# Attiny_bot.net
KiCad netlist of a schematic drawn in EAGLE
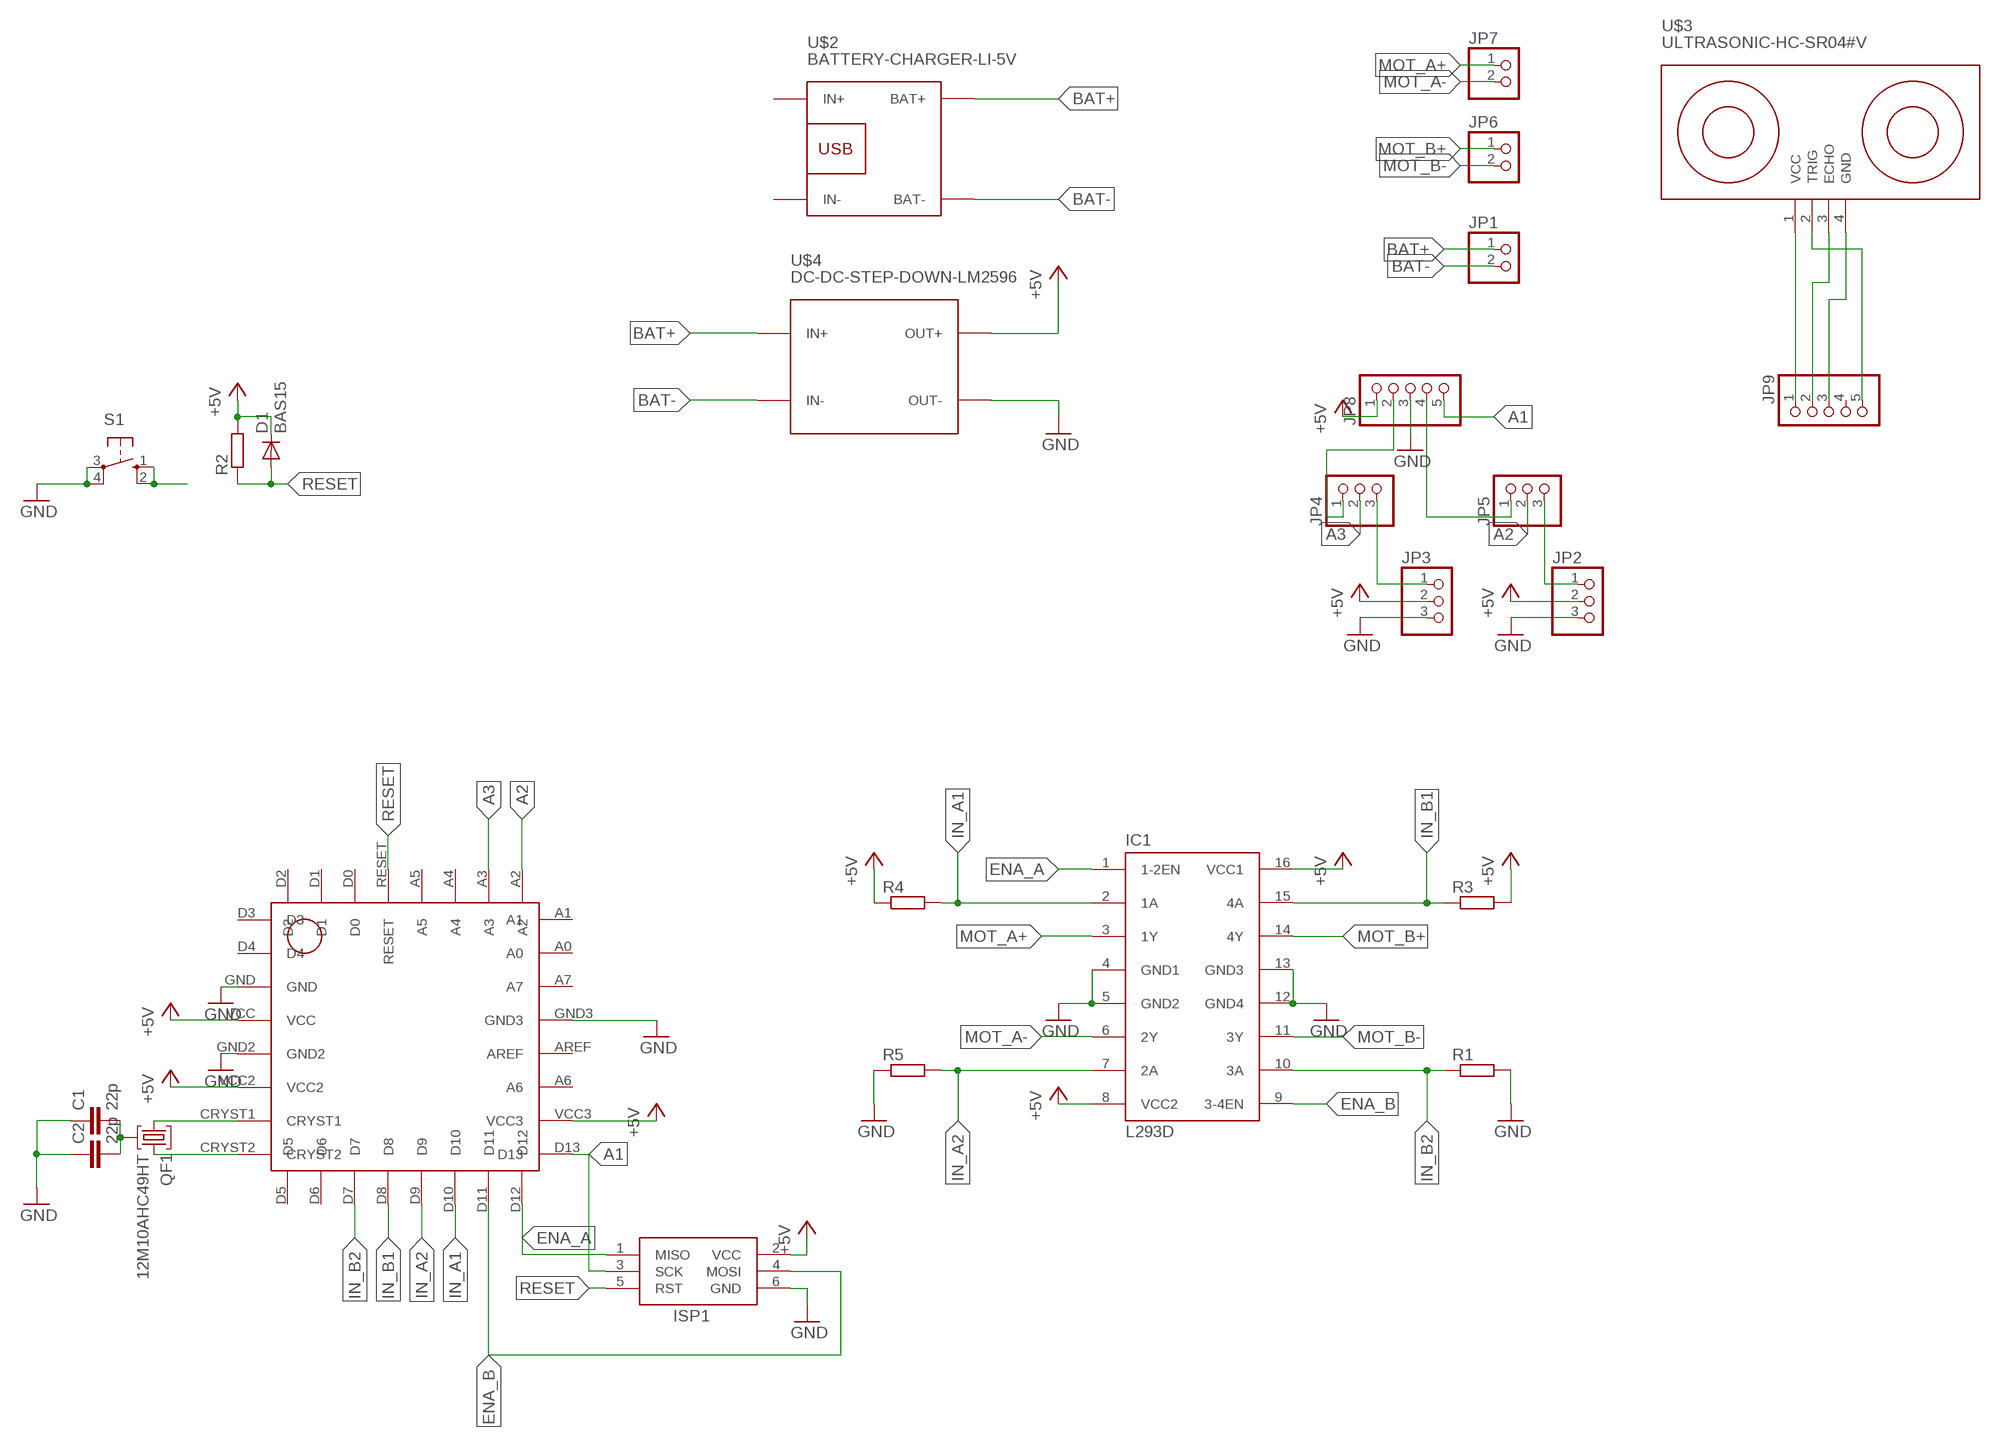
[diagram p0: schematic, sheet 1]

(export (version "E")
  (design (tool "Eeschema 10.0.6"))
  (components
    (comp (ref "C1")
      (value "22p")
      (footprint "eagle-import:C1206")
      (libsource (lib "eagle-import") (part "C-EUC1206"))
    )
    (comp (ref "C2")
      (value "22p")
      (footprint "eagle-import:C1206")
      (libsource (lib "eagle-import") (part "C-EUC1206"))
    )
    (comp (ref "D1")
      (value "BAS15")
      (footprint "eagle-import:DO34-7")
      (libsource (lib "eagle-import") (part "BAS15"))
    )
    (comp (ref "IC1")
      (value "L293D")
      (footprint "eagle-import:DIL16")
      (libsource (lib "eagle-import") (part "L293D"))
    )
    (comp (ref "ISP1")
      (value "AVRISP-6")
      (footprint "eagle-import:AVRISP")
      (libsource (lib "eagle-import") (part "AVRISP-6"))
    )
    (comp (ref "JP1")
      (value "PINHD-1X2")
      (footprint "eagle-import:1X02")
      (libsource (lib "eagle-import") (part "PINHD-1X2"))
    )
    (comp (ref "JP2")
      (value "PINHD-1X3")
      (footprint "eagle-import:1X03")
      (libsource (lib "eagle-import") (part "PINHD-1X3"))
    )
    (comp (ref "JP3")
      (value "PINHD-1X3")
      (footprint "eagle-import:1X03")
      (libsource (lib "eagle-import") (part "PINHD-1X3"))
    )
    (comp (ref "JP4")
      (value "PINHD-1X3")
      (footprint "eagle-import:1X03")
      (libsource (lib "eagle-import") (part "PINHD-1X3"))
    )
    (comp (ref "JP5")
      (value "PINHD-1X3")
      (footprint "eagle-import:1X03")
      (libsource (lib "eagle-import") (part "PINHD-1X3"))
    )
    (comp (ref "JP6")
      (value "PINHD-1X2")
      (footprint "eagle-import:1X02")
      (libsource (lib "eagle-import") (part "PINHD-1X2"))
    )
    (comp (ref "JP7")
      (value "PINHD-1X2")
      (footprint "eagle-import:1X02")
      (libsource (lib "eagle-import") (part "PINHD-1X2"))
    )
    (comp (ref "JP8")
      (value "PINHD-1X5")
      (footprint "eagle-import:1X05")
      (libsource (lib "eagle-import") (part "PINHD-1X5"))
    )
    (comp (ref "JP9")
      (value "PINHD-1X5")
      (footprint "eagle-import:1X05")
      (libsource (lib "eagle-import") (part "PINHD-1X5"))
    )
    (comp (ref "QF1")
      (value "12M10AHC49HT")
      (footprint "eagle-import:HC49U")
      (libsource (lib "eagle-import") (part "12M10AHC49HT"))
    )
    (comp (ref "R1")
      (value "R-EU_R1206")
      (footprint "eagle-import:R1206")
      (libsource (lib "eagle-import") (part "R-EU_R1206"))
    )
    (comp (ref "R2")
      (value "R-EU_R1206")
      (footprint "eagle-import:R1206")
      (libsource (lib "eagle-import") (part "R-EU_R1206"))
    )
    (comp (ref "R3")
      (value "R-EU_R1206")
      (footprint "eagle-import:R1206")
      (libsource (lib "eagle-import") (part "R-EU_R1206"))
    )
    (comp (ref "R4")
      (value "R-EU_R1206")
      (footprint "eagle-import:R1206")
      (libsource (lib "eagle-import") (part "R-EU_R1206"))
    )
    (comp (ref "R5")
      (value "R-EU_R1206")
      (footprint "eagle-import:R1206")
      (libsource (lib "eagle-import") (part "R-EU_R1206"))
    )
    (comp (ref "S1")
      (value "10-XX")
      (footprint "eagle-import:B3F-10XX")
      (fields (field (name "MPN") "B3F-1000"))
      (libsource (lib "eagle-import") (part "10-XX"))
    )
    (comp (ref "U$1")
      (value "PROCESSOR")
      (footprint "eagle-import:PROCESOR")
      (libsource (lib "eagle-import") (part "PROCESSOR"))
    )
    (comp (ref "U$2")
      (value "BATTERY-CHARGER-LI-5V")
      (footprint "eagle-import:BATTERY-CHARGER-LI-5V")
      (libsource (lib "eagle-import") (part "BATTERY-CHARGER-LI-5V"))
    )
    (comp (ref "U$3")
      (value "ULTRASONIC-HC-SR04#V")
      (footprint "eagle-import:ULTRASONIC-HC-SR04#V")
      (libsource (lib "eagle-import") (part "ULTRASONIC-HC-SR04#V"))
    )
    (comp (ref "U$4")
      (value "DC-DC-STEP-DOWN-LM2596")
      (footprint "eagle-import:DC-DC-STEP-DOWN-LM2596")
      (libsource (lib "eagle-import") (part "DC-DC-STEP-DOWN-LM2596"))
    )
  )
  (nets
    (net (code "1") (name "+5V") (class "Default")
      (node (ref "D1") (pin "C") (pinfunction "C_C") (pintype "passive"))
      (node (ref "IC1") (pin "16") (pinfunction "VCC1_16") (pintype "power_in"))
      (node (ref "IC1") (pin "8") (pinfunction "VCC2_8") (pintype "power_in"))
      (node (ref "ISP1") (pin "2") (pinfunction "VCC_2") (pintype "power_in"))
      (node (ref "JP2") (pin "2") (pinfunction "2_2") (pintype "passive"))
      (node (ref "JP3") (pin "2") (pinfunction "2_2") (pintype "passive"))
      (node (ref "JP8") (pin "1") (pinfunction "1_1") (pintype "passive"))
      (node (ref "R2") (pin "2") (pinfunction "2_2") (pintype "passive"))
      (node (ref "R3") (pin "2") (pinfunction "2_2") (pintype "passive"))
      (node (ref "R4") (pin "1") (pinfunction "1_1") (pintype "passive"))
      (node (ref "U$1") (pin "VCC") (pinfunction "VCC_VCC") (pintype "bidirectional"))
      (node (ref "U$1") (pin "VCC2") (pinfunction "VCC2_VCC2") (pintype "bidirectional"))
      (node (ref "U$1") (pin "VCC3") (pinfunction "VCC3_VCC3") (pintype "bidirectional"))
      (node (ref "U$4") (pin "OUT+") (pinfunction "OUT+_OUT+") (pintype "bidirectional"))
    )
    (net (code "2") (name "A1") (class "Default")
      (node (ref "ISP1") (pin "3") (pinfunction "SCK_3") (pintype "output"))
      (node (ref "JP8") (pin "5") (pinfunction "5_5") (pintype "passive"))
      (node (ref "U$1") (pin "D13") (pinfunction "D13_D13") (pintype "bidirectional"))
    )
    (net (code "3") (name "A2") (class "Default")
      (node (ref "JP5") (pin "2") (pinfunction "2_2") (pintype "passive"))
      (node (ref "U$1") (pin "A2") (pinfunction "A2_A2") (pintype "bidirectional"))
    )
    (net (code "4") (name "A3") (class "Default")
      (node (ref "JP4") (pin "2") (pinfunction "2_2") (pintype "passive"))
      (node (ref "U$1") (pin "A3") (pinfunction "A3_A3") (pintype "bidirectional"))
    )
    (net (code "5") (name "BAT+") (class "Default")
      (node (ref "JP1") (pin "1") (pinfunction "1_1") (pintype "passive"))
      (node (ref "U$2") (pin "BAT+") (pinfunction "BAT+_BAT+") (pintype "bidirectional"))
      (node (ref "U$4") (pin "IN+") (pinfunction "IN+_IN+") (pintype "bidirectional"))
    )
    (net (code "6") (name "BAT-") (class "Default")
      (node (ref "JP1") (pin "2") (pinfunction "2_2") (pintype "passive"))
      (node (ref "U$2") (pin "BAT-") (pinfunction "BAT-_BAT-") (pintype "bidirectional"))
      (node (ref "U$4") (pin "IN-") (pinfunction "IN-_IN-") (pintype "bidirectional"))
    )
    (net (code "7") (name "ENA_A") (class "Default")
      (node (ref "IC1") (pin "1") (pinfunction "1-2EN_1") (pintype "input"))
      (node (ref "ISP1") (pin "1") (pinfunction "MISO_1") (pintype "input"))
      (node (ref "U$1") (pin "D12") (pinfunction "D12_D12") (pintype "bidirectional"))
    )
    (net (code "8") (name "ENA_B") (class "Default")
      (node (ref "IC1") (pin "9") (pinfunction "3-4EN_9") (pintype "input"))
      (node (ref "ISP1") (pin "4") (pinfunction "MOSI_4") (pintype "output"))
      (node (ref "U$1") (pin "D11") (pinfunction "D11_D11") (pintype "bidirectional"))
    )
    (net (code "9") (name "GND") (class "Default")
      (node (ref "C1") (pin "1") (pinfunction "1_1") (pintype "passive"))
      (node (ref "C2") (pin "1") (pinfunction "1_1") (pintype "passive"))
      (node (ref "IC1") (pin "12") (pinfunction "GND4_12") (pintype "power_in"))
      (node (ref "IC1") (pin "13") (pinfunction "GND3_13") (pintype "power_in"))
      (node (ref "IC1") (pin "4") (pinfunction "GND1_4") (pintype "power_in"))
      (node (ref "IC1") (pin "5") (pinfunction "GND2_5") (pintype "power_in"))
      (node (ref "ISP1") (pin "6") (pinfunction "GND_6") (pintype "power_in"))
      (node (ref "JP2") (pin "3") (pinfunction "3_3") (pintype "passive"))
      (node (ref "JP3") (pin "3") (pinfunction "3_3") (pintype "passive"))
      (node (ref "JP8") (pin "3") (pinfunction "3_3") (pintype "passive"))
      (node (ref "R1") (pin "2") (pinfunction "2_2") (pintype "passive"))
      (node (ref "R5") (pin "1") (pinfunction "1_1") (pintype "passive"))
      (node (ref "S1") (pin "3") (pinfunction "P_3") (pintype "passive"))
      (node (ref "S1") (pin "4") (pinfunction "P1_4") (pintype "passive"))
      (node (ref "U$1") (pin "GND") (pinfunction "GND_GND") (pintype "bidirectional"))
      (node (ref "U$1") (pin "GND2") (pinfunction "GND2_GND2") (pintype "bidirectional"))
      (node (ref "U$1") (pin "GND3") (pinfunction "GND3_GND3") (pintype "bidirectional"))
      (node (ref "U$4") (pin "OUT-") (pinfunction "OUT-_OUT-") (pintype "bidirectional"))
    )
    (net (code "10") (name "IN_A1") (class "Default")
      (node (ref "IC1") (pin "2") (pinfunction "1A_2") (pintype "input"))
      (node (ref "R4") (pin "2") (pinfunction "2_2") (pintype "passive"))
      (node (ref "U$1") (pin "D10") (pinfunction "D10_D10") (pintype "bidirectional"))
    )
    (net (code "11") (name "IN_A2") (class "Default")
      (node (ref "IC1") (pin "7") (pinfunction "2A_7") (pintype "input"))
      (node (ref "R5") (pin "2") (pinfunction "2_2") (pintype "passive"))
      (node (ref "U$1") (pin "D9") (pinfunction "D9_D9") (pintype "bidirectional"))
    )
    (net (code "12") (name "IN_B1") (class "Default")
      (node (ref "IC1") (pin "15") (pinfunction "4A_15") (pintype "input"))
      (node (ref "R3") (pin "1") (pinfunction "1_1") (pintype "passive"))
      (node (ref "U$1") (pin "D8") (pinfunction "D8_D8") (pintype "bidirectional"))
    )
    (net (code "13") (name "IN_B2") (class "Default")
      (node (ref "IC1") (pin "10") (pinfunction "3A_10") (pintype "input"))
      (node (ref "R1") (pin "1") (pinfunction "1_1") (pintype "passive"))
      (node (ref "U$1") (pin "D7") (pinfunction "D7_D7") (pintype "bidirectional"))
    )
    (net (code "14") (name "MOT_A+") (class "Default")
      (node (ref "IC1") (pin "3") (pinfunction "1Y_3") (pintype "output"))
      (node (ref "JP7") (pin "1") (pinfunction "1_1") (pintype "passive"))
    )
    (net (code "15") (name "MOT_A-") (class "Default")
      (node (ref "IC1") (pin "6") (pinfunction "2Y_6") (pintype "output"))
      (node (ref "JP7") (pin "2") (pinfunction "2_2") (pintype "passive"))
    )
    (net (code "16") (name "MOT_B+") (class "Default")
      (node (ref "IC1") (pin "14") (pinfunction "4Y_14") (pintype "output"))
      (node (ref "JP6") (pin "1") (pinfunction "1_1") (pintype "passive"))
    )
    (net (code "17") (name "MOT_B-") (class "Default")
      (node (ref "IC1") (pin "11") (pinfunction "3Y_11") (pintype "output"))
      (node (ref "JP6") (pin "2") (pinfunction "2_2") (pintype "passive"))
    )
    (net (code "18") (name "Net-(C1-Pad2)") (class "Default")
      (node (ref "C1") (pin "2") (pinfunction "2_2") (pintype "passive"))
      (node (ref "C2") (pin "2") (pinfunction "2_2") (pintype "passive"))
      (node (ref "QF1") (pin "2") (pinfunction "2_2") (pintype "passive"))
    )
    (net (code "19") (name "Net-(JP2-Pad1)") (class "Default")
      (node (ref "JP2") (pin "1") (pinfunction "1_1") (pintype "passive"))
      (node (ref "JP5") (pin "3") (pinfunction "3_3") (pintype "passive"))
    )
    (net (code "20") (name "Net-(JP3-Pad1)") (class "Default")
      (node (ref "JP3") (pin "1") (pinfunction "1_1") (pintype "passive"))
      (node (ref "JP4") (pin "3") (pinfunction "3_3") (pintype "passive"))
    )
    (net (code "21") (name "Net-(JP4-Pad1)") (class "Default")
      (node (ref "JP4") (pin "1") (pinfunction "1_1") (pintype "passive"))
      (node (ref "JP8") (pin "2") (pinfunction "2_2") (pintype "passive"))
    )
    (net (code "22") (name "Net-(JP5-Pad1)") (class "Default")
      (node (ref "JP5") (pin "1") (pinfunction "1_1") (pintype "passive"))
      (node (ref "JP8") (pin "4") (pinfunction "4_4") (pintype "passive"))
    )
    (net (code "23") (name "Net-(QF1-Pad1)") (class "Default")
      (node (ref "QF1") (pin "1") (pinfunction "1_1") (pintype "passive"))
      (node (ref "U$1") (pin "CRYST1") (pinfunction "CRYST1_CRYST1") (pintype "bidirectional"))
    )
    (net (code "24") (name "Net-(QF1-Pad3)") (class "Default")
      (node (ref "QF1") (pin "3") (pinfunction "3_3") (pintype "passive"))
      (node (ref "U$1") (pin "CRYST2") (pinfunction "CRYST2_CRYST2") (pintype "bidirectional"))
    )
    (net (code "25") (name "Net-(S1-S)") (class "Default")
      (node (ref "S1") (pin "1") (pinfunction "S_1") (pintype "passive"))
      (node (ref "S1") (pin "2") (pinfunction "S1_2") (pintype "passive"))
    )
    (net (code "26") (name "Net-(U$3-ECHO)") (class "Default")
      (node (ref "JP9") (pin "2") (pinfunction "2_2") (pintype "passive"))
      (node (ref "U$3") (pin "3") (pinfunction "ECHO_3") (pintype "output"))
    )
    (net (code "27") (name "Net-(U$3-GND)") (class "Default")
      (node (ref "JP9") (pin "3") (pinfunction "3_3") (pintype "passive"))
      (node (ref "U$3") (pin "4") (pinfunction "GND_4") (pintype "power_in"))
    )
    (net (code "28") (name "Net-(U$3-TRIG)") (class "Default")
      (node (ref "JP9") (pin "5") (pinfunction "5_5") (pintype "passive"))
      (node (ref "U$3") (pin "2") (pinfunction "TRIG_2") (pintype "input"))
    )
    (net (code "29") (name "Net-(U$3-VCC)") (class "Default")
      (node (ref "JP9") (pin "1") (pinfunction "1_1") (pintype "passive"))
      (node (ref "U$3") (pin "1") (pinfunction "VCC_1") (pintype "power_in"))
    )
    (net (code "30") (name "RESET") (class "Default")
      (node (ref "D1") (pin "A") (pinfunction "A_A") (pintype "passive"))
      (node (ref "ISP1") (pin "5") (pinfunction "RST_5") (pintype "output"))
      (node (ref "R2") (pin "1") (pinfunction "1_1") (pintype "passive"))
      (node (ref "U$1") (pin "RESET") (pinfunction "RESET_RESET") (pintype "bidirectional"))
    )
    (net (code "31") (name "unconnected-(JP9-Pad4)") (class "Default")
      (node (ref "JP9") (pin "4") (pinfunction "4_4") (pintype "passive"))
    )
    (net (code "32") (name "unconnected-(U$1-PadA0)") (class "Default")
      (node (ref "U$1") (pin "A0") (pinfunction "A0_A0") (pintype "bidirectional"))
    )
    (net (code "33") (name "unconnected-(U$1-PadA1)") (class "Default")
      (node (ref "U$1") (pin "A1") (pinfunction "A1_A1") (pintype "bidirectional"))
    )
    (net (code "34") (name "unconnected-(U$1-PadA4)") (class "Default")
      (node (ref "U$1") (pin "A4") (pinfunction "A4_A4") (pintype "bidirectional"))
    )
    (net (code "35") (name "unconnected-(U$1-PadA5)") (class "Default")
      (node (ref "U$1") (pin "A5") (pinfunction "A5_A5") (pintype "bidirectional"))
    )
    (net (code "36") (name "unconnected-(U$1-PadA6)") (class "Default")
      (node (ref "U$1") (pin "A6") (pinfunction "A6_A6") (pintype "bidirectional"))
    )
    (net (code "37") (name "unconnected-(U$1-PadA7)") (class "Default")
      (node (ref "U$1") (pin "A7") (pinfunction "A7_A7") (pintype "bidirectional"))
    )
    (net (code "38") (name "unconnected-(U$1-PadAREF)") (class "Default")
      (node (ref "U$1") (pin "AREF") (pinfunction "AREF_AREF") (pintype "bidirectional"))
    )
    (net (code "39") (name "unconnected-(U$1-PadD0)") (class "Default")
      (node (ref "U$1") (pin "D0") (pinfunction "D0_D0") (pintype "bidirectional"))
    )
    (net (code "40") (name "unconnected-(U$1-PadD1)") (class "Default")
      (node (ref "U$1") (pin "D1") (pinfunction "D1_D1") (pintype "bidirectional"))
    )
    (net (code "41") (name "unconnected-(U$1-PadD2)") (class "Default")
      (node (ref "U$1") (pin "D2") (pinfunction "D2_D2") (pintype "bidirectional"))
    )
    (net (code "42") (name "unconnected-(U$1-PadD3)") (class "Default")
      (node (ref "U$1") (pin "D3") (pinfunction "D3_D3") (pintype "bidirectional"))
    )
    (net (code "43") (name "unconnected-(U$1-PadD4)") (class "Default")
      (node (ref "U$1") (pin "D4") (pinfunction "D4_D4") (pintype "bidirectional"))
    )
    (net (code "44") (name "unconnected-(U$1-PadD5)") (class "Default")
      (node (ref "U$1") (pin "D5") (pinfunction "D5_D5") (pintype "bidirectional"))
    )
    (net (code "45") (name "unconnected-(U$1-PadD6)") (class "Default")
      (node (ref "U$1") (pin "D6") (pinfunction "D6_D6") (pintype "bidirectional"))
    )
    (net (code "46") (name "unconnected-(U$2-PadIN+)") (class "Default")
      (node (ref "U$2") (pin "IN+") (pinfunction "IN+_IN+") (pintype "bidirectional"))
    )
    (net (code "47") (name "unconnected-(U$2-PadIN-)") (class "Default")
      (node (ref "U$2") (pin "IN-") (pinfunction "IN-_IN-") (pintype "bidirectional"))
    )
  )
)
